# design.net
KiCad netlist of a schematic drawn in EasyEDA Pro
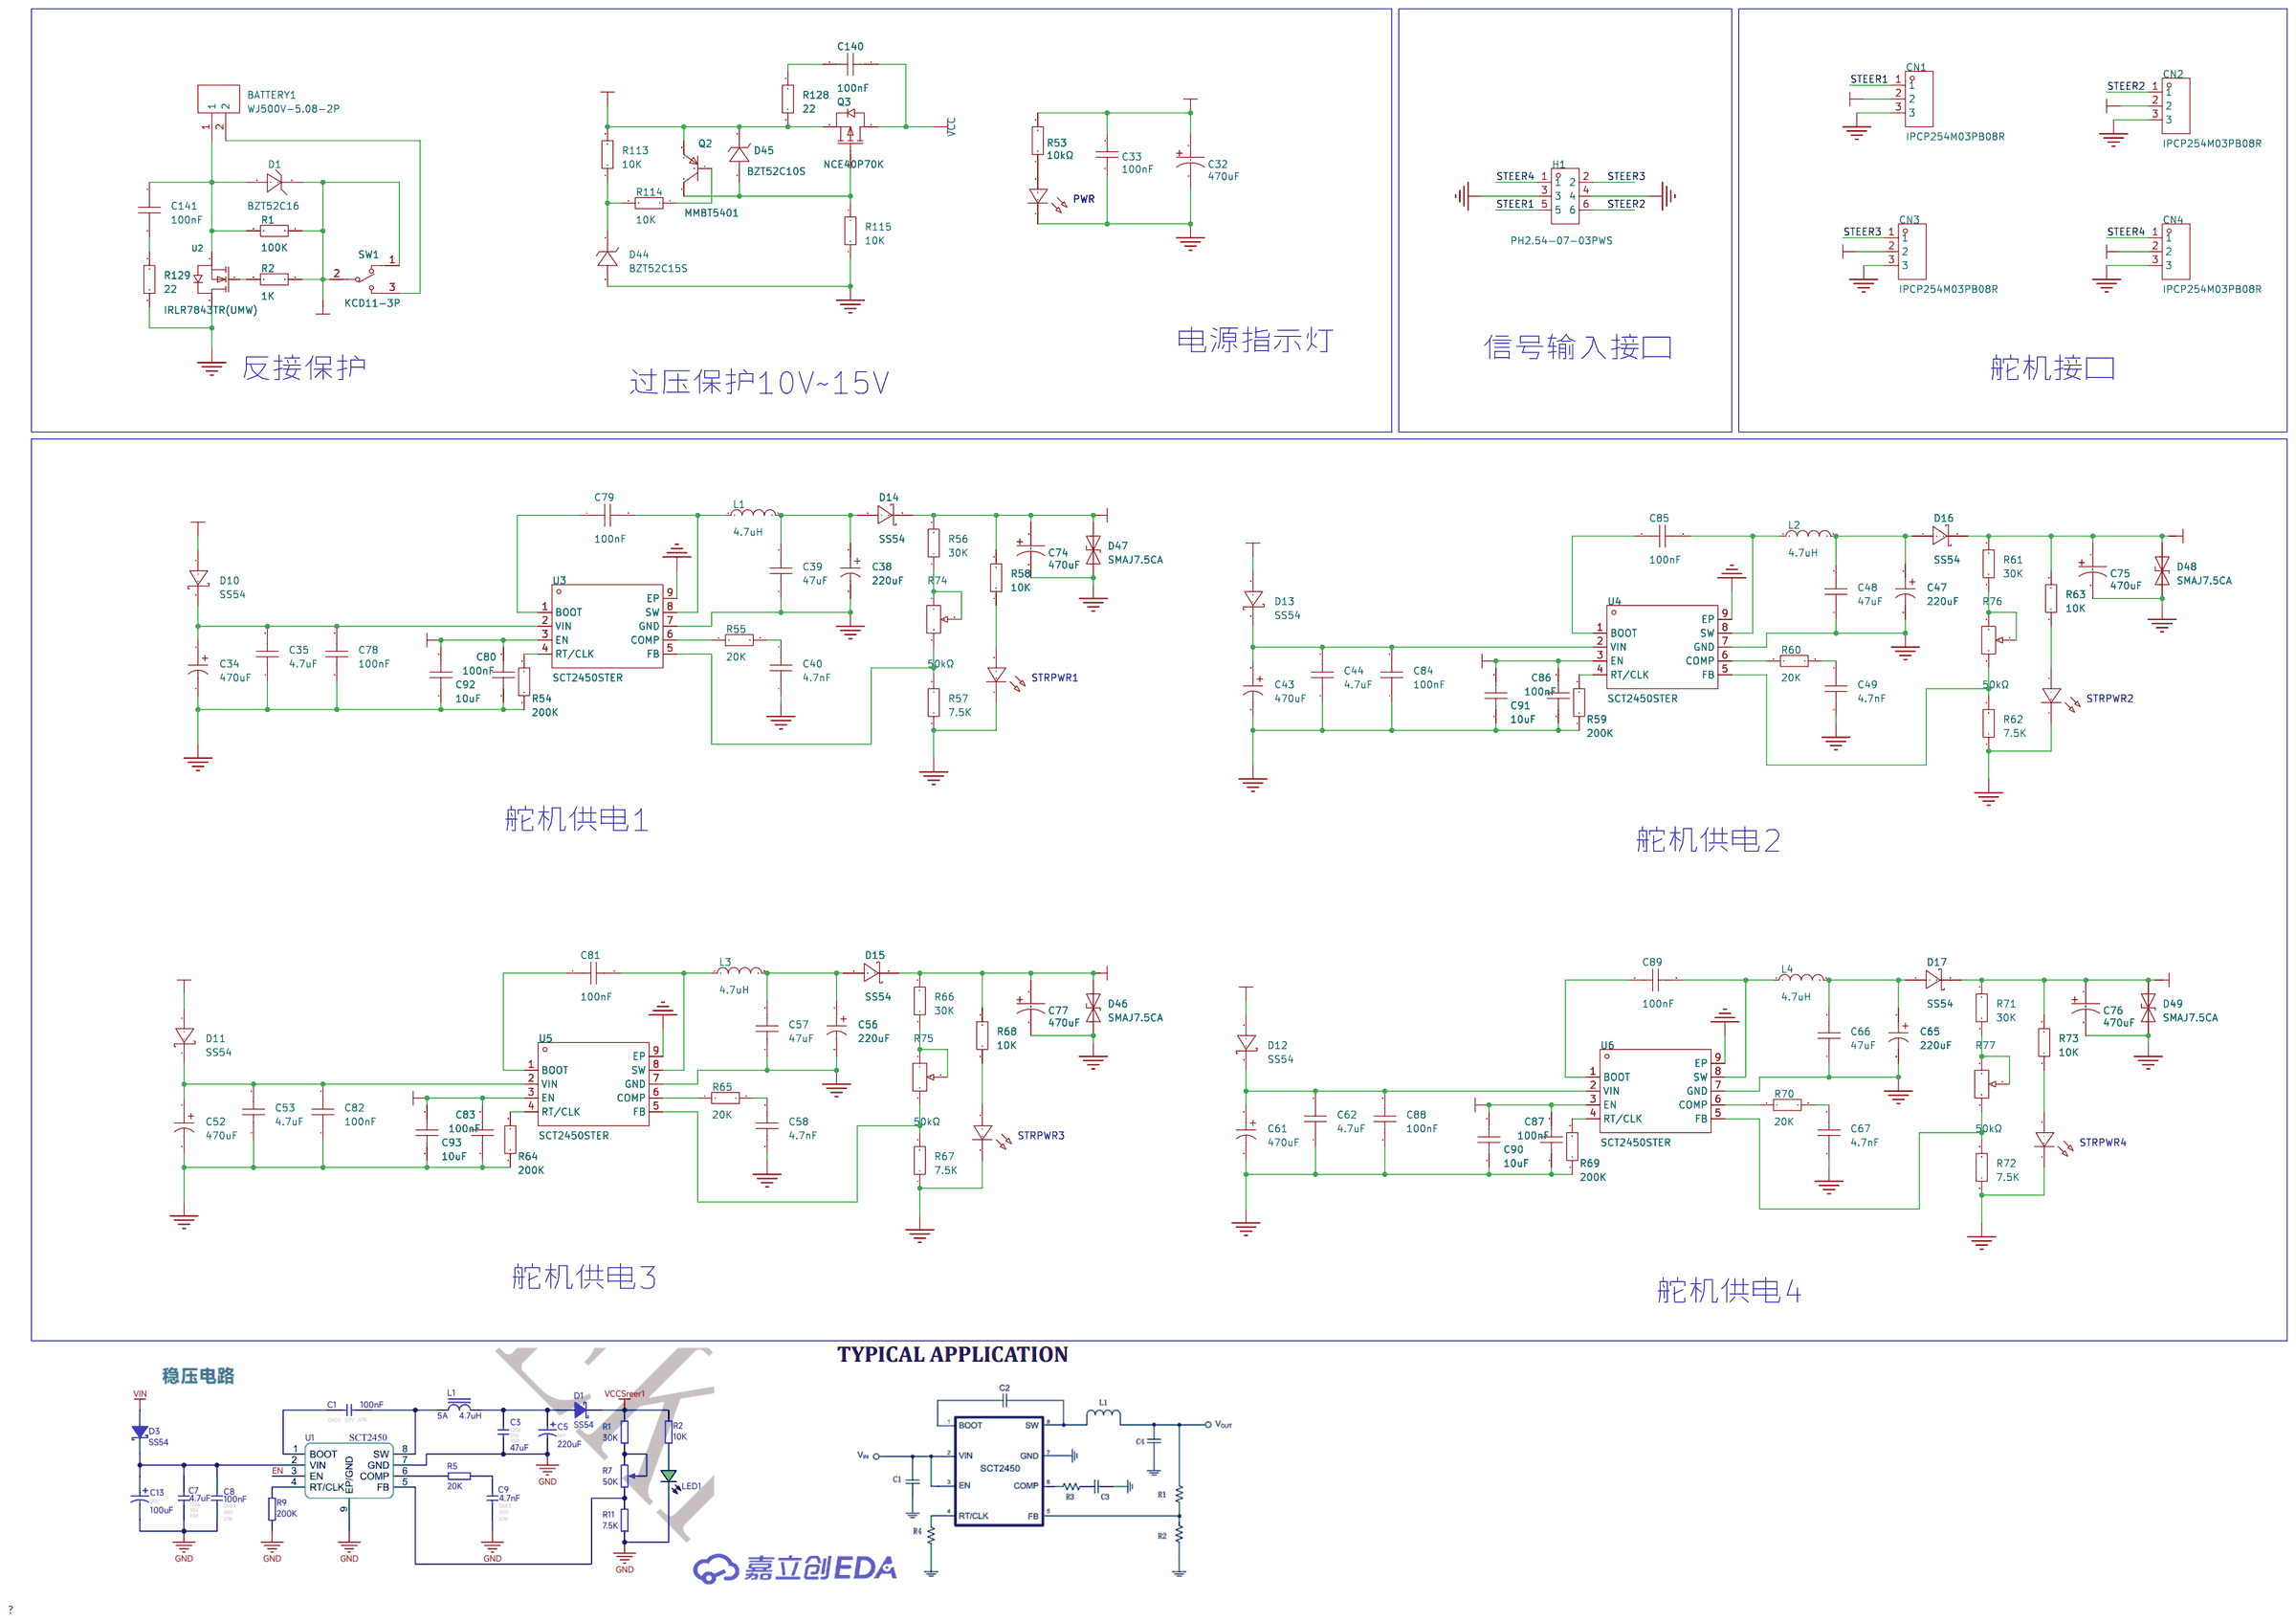
[diagram p0: schematic sheet]

(export (version "E")
  (design (tool "Eeschema 10.0.6"))
  (components
    (comp (ref "BATTERY1")
      (value "WJ500V-5.08-2P")
      (footprint "easyedapro:CONN-TH_2P-P5.00_WJ500V-5.08-2P")
      (fields (field (name "Manufacturer") "KANGNEX(康奈克斯电气)"))
      (libsource (lib "easyedapro") (part "WJ500V-5.08-2P-14-00A"))
    )
    (comp (ref "C32")
      (value "470uF")
      (footprint "easyedapro:CAP-TH_BD8.0-P3.50-D0.6-FD")
      (fields (field (name "Manufacturer Part") "HS1C477M0811PC") (field (name "Manufacturer") "HONOR(荣誉)"))
      (libsource (lib "easyedapro") (part "470uF"))
    )
    (comp (ref "C33")
      (value "100nF")
      (footprint "easyedapro:C0805")
      (fields
        (field (name "Manufacturer Part") "CC0805KRX7R9BB104")
        (field (name "Manufacturer") "YAGEO(国巨)")
      )
      (libsource (lib "easyedapro") (part "100nF"))
    )
    (comp (ref "C34")
      (value "470uF")
      (footprint "easyedapro:CAP-SMD_BD8.0-L8.3-W8.3-FD")
      (description "容值:470uF;精度:±20%;额定电压:25V;纹波电流:280mA@120Hz;等效串联电阻:-;")
      (fields (field (name "Manufacturer Part") "RST470UF25V032") (field (name "Manufacturer") "KNSCHA(科尼盛)"))
      (libsource (lib "easyedapro") (part "RST470UF25V032"))
    )
    (comp (ref "C35")
      (value "4.7uF")
      (footprint "easyedapro:C1206")
      (libsource (lib "easyedapro") (part "CapAcitance"))
    )
    (comp (ref "C38")
      (value "220uF")
      (footprint "easyedapro:CAP-SMD_BD8.0-L8.3-W8.3-FD")
      (description "容值:470uF;精度:±20%;额定电压:25V;纹波电流:280mA@120Hz;等效串联电阻:-;")
      (fields (field (name "Manufacturer Part") "RST470UF25V032") (field (name "Manufacturer") "KNSCHA(科尼盛)"))
      (libsource (lib "easyedapro") (part "RST470UF25V032"))
    )
    (comp (ref "C39")
      (value "47uF")
      (footprint "easyedapro:C1206")
      (libsource (lib "easyedapro") (part "CapAcitance"))
    )
    (comp (ref "C40")
      (value "4.7nF")
      (footprint "easyedapro:C1206")
      (libsource (lib "easyedapro") (part "CapAcitance"))
    )
    (comp (ref "C43")
      (value "470uF")
      (footprint "easyedapro:CAP-SMD_BD8.0-L8.3-W8.3-FD")
      (description "容值:470uF;精度:±20%;额定电压:25V;纹波电流:280mA@120Hz;等效串联电阻:-;")
      (fields (field (name "Manufacturer Part") "RST470UF25V032") (field (name "Manufacturer") "KNSCHA(科尼盛)"))
      (libsource (lib "easyedapro") (part "RST470UF25V032"))
    )
    (comp (ref "C44")
      (value "4.7uF")
      (footprint "easyedapro:C1206")
      (libsource (lib "easyedapro") (part "CapAcitance"))
    )
    (comp (ref "C47")
      (value "220uF")
      (footprint "easyedapro:CAP-SMD_BD8.0-L8.3-W8.3-FD")
      (description "容值:470uF;精度:±20%;额定电压:25V;纹波电流:280mA@120Hz;等效串联电阻:-;")
      (fields (field (name "Manufacturer Part") "RST470UF25V032") (field (name "Manufacturer") "KNSCHA(科尼盛)"))
      (libsource (lib "easyedapro") (part "RST470UF25V032"))
    )
    (comp (ref "C48")
      (value "47uF")
      (footprint "easyedapro:C1206")
      (libsource (lib "easyedapro") (part "CapAcitance"))
    )
    (comp (ref "C49")
      (value "4.7nF")
      (footprint "easyedapro:C1206")
      (libsource (lib "easyedapro") (part "CapAcitance"))
    )
    (comp (ref "C52")
      (value "470uF")
      (footprint "easyedapro:CAP-SMD_BD8.0-L8.3-W8.3-FD")
      (description "容值:470uF;精度:±20%;额定电压:25V;纹波电流:280mA@120Hz;等效串联电阻:-;")
      (fields (field (name "Manufacturer Part") "RST470UF25V032") (field (name "Manufacturer") "KNSCHA(科尼盛)"))
      (libsource (lib "easyedapro") (part "RST470UF25V032"))
    )
    (comp (ref "C53")
      (value "4.7uF")
      (footprint "easyedapro:C1206")
      (libsource (lib "easyedapro") (part "CapAcitance"))
    )
    (comp (ref "C56")
      (value "220uF")
      (footprint "easyedapro:CAP-SMD_BD8.0-L8.3-W8.3-FD")
      (description "容值:470uF;精度:±20%;额定电压:25V;纹波电流:280mA@120Hz;等效串联电阻:-;")
      (fields (field (name "Manufacturer Part") "RST470UF25V032") (field (name "Manufacturer") "KNSCHA(科尼盛)"))
      (libsource (lib "easyedapro") (part "RST470UF25V032"))
    )
    (comp (ref "C57")
      (value "47uF")
      (footprint "easyedapro:C1206")
      (libsource (lib "easyedapro") (part "CapAcitance"))
    )
    (comp (ref "C58")
      (value "4.7nF")
      (footprint "easyedapro:C1206")
      (libsource (lib "easyedapro") (part "CapAcitance"))
    )
    (comp (ref "C61")
      (value "470uF")
      (footprint "easyedapro:CAP-SMD_BD8.0-L8.3-W8.3-FD")
      (description "容值:470uF;精度:±20%;额定电压:25V;纹波电流:280mA@120Hz;等效串联电阻:-;")
      (fields (field (name "Manufacturer Part") "RST470UF25V032") (field (name "Manufacturer") "KNSCHA(科尼盛)"))
      (libsource (lib "easyedapro") (part "RST470UF25V032"))
    )
    (comp (ref "C62")
      (value "4.7uF")
      (footprint "easyedapro:C1206")
      (libsource (lib "easyedapro") (part "CapAcitance"))
    )
    (comp (ref "C65")
      (value "220uF")
      (footprint "easyedapro:CAP-SMD_BD8.0-L8.3-W8.3-FD")
      (description "容值:470uF;精度:±20%;额定电压:25V;纹波电流:280mA@120Hz;等效串联电阻:-;")
      (fields (field (name "Manufacturer Part") "RST470UF25V032") (field (name "Manufacturer") "KNSCHA(科尼盛)"))
      (libsource (lib "easyedapro") (part "RST470UF25V032"))
    )
    (comp (ref "C66")
      (value "47uF")
      (footprint "easyedapro:C1206")
      (libsource (lib "easyedapro") (part "CapAcitance"))
    )
    (comp (ref "C67")
      (value "4.7nF")
      (footprint "easyedapro:C1206")
      (libsource (lib "easyedapro") (part "CapAcitance"))
    )
    (comp (ref "C74")
      (value "470uF")
      (footprint "easyedapro:CAP-TH_BD8.0-P3.50-D0.6-FD")
      (fields (field (name "Manufacturer Part") "HS1C477M0811PC") (field (name "Manufacturer") "HONOR(荣誉)"))
      (libsource (lib "easyedapro") (part "470uF"))
    )
    (comp (ref "C75")
      (value "470uF")
      (footprint "easyedapro:CAP-TH_BD8.0-P3.50-D0.6-FD")
      (fields (field (name "Manufacturer Part") "HS1C477M0811PC") (field (name "Manufacturer") "HONOR(荣誉)"))
      (libsource (lib "easyedapro") (part "470uF"))
    )
    (comp (ref "C76")
      (value "470uF")
      (footprint "easyedapro:CAP-TH_BD8.0-P3.50-D0.6-FD")
      (fields (field (name "Manufacturer Part") "HS1C477M0811PC") (field (name "Manufacturer") "HONOR(荣誉)"))
      (libsource (lib "easyedapro") (part "470uF"))
    )
    (comp (ref "C77")
      (value "470uF")
      (footprint "easyedapro:CAP-TH_BD8.0-P3.50-D0.6-FD")
      (fields (field (name "Manufacturer Part") "HS1C477M0811PC") (field (name "Manufacturer") "HONOR(荣誉)"))
      (libsource (lib "easyedapro") (part "470uF"))
    )
    (comp (ref "C78")
      (value "100nF")
      (footprint "easyedapro:C1206")
      (libsource (lib "easyedapro") (part "CapAcitance"))
    )
    (comp (ref "C79")
      (value "100nF")
      (footprint "easyedapro:C1206")
      (libsource (lib "easyedapro") (part "CapAcitance"))
    )
    (comp (ref "C80")
      (value "100nF")
      (footprint "easyedapro:C1206")
      (libsource (lib "easyedapro") (part "CapAcitance"))
    )
    (comp (ref "C81")
      (value "100nF")
      (footprint "easyedapro:C1206")
      (libsource (lib "easyedapro") (part "CapAcitance"))
    )
    (comp (ref "C82")
      (value "100nF")
      (footprint "easyedapro:C1206")
      (libsource (lib "easyedapro") (part "CapAcitance"))
    )
    (comp (ref "C83")
      (value "100nF")
      (footprint "easyedapro:C1206")
      (libsource (lib "easyedapro") (part "CapAcitance"))
    )
    (comp (ref "C84")
      (value "100nF")
      (footprint "easyedapro:C1206")
      (libsource (lib "easyedapro") (part "CapAcitance"))
    )
    (comp (ref "C85")
      (value "100nF")
      (footprint "easyedapro:C1206")
      (libsource (lib "easyedapro") (part "CapAcitance"))
    )
    (comp (ref "C86")
      (value "100nF")
      (footprint "easyedapro:C1206")
      (libsource (lib "easyedapro") (part "CapAcitance"))
    )
    (comp (ref "C87")
      (value "100nF")
      (footprint "easyedapro:C1206")
      (libsource (lib "easyedapro") (part "CapAcitance"))
    )
    (comp (ref "C88")
      (value "100nF")
      (footprint "easyedapro:C1206")
      (libsource (lib "easyedapro") (part "CapAcitance"))
    )
    (comp (ref "C89")
      (value "100nF")
      (footprint "easyedapro:C1206")
      (libsource (lib "easyedapro") (part "CapAcitance"))
    )
    (comp (ref "C90")
      (value "10uF")
      (footprint "easyedapro:C1206")
      (libsource (lib "easyedapro") (part "CapAcitance"))
    )
    (comp (ref "C91")
      (value "10uF")
      (footprint "easyedapro:C1206")
      (libsource (lib "easyedapro") (part "CapAcitance"))
    )
    (comp (ref "C92")
      (value "10uF")
      (footprint "easyedapro:C1206")
      (libsource (lib "easyedapro") (part "CapAcitance"))
    )
    (comp (ref "C93")
      (value "10uF")
      (footprint "easyedapro:C1206")
      (libsource (lib "easyedapro") (part "CapAcitance"))
    )
    (comp (ref "C140")
      (value "100nF")
      (footprint "easyedapro:C1206")
      (libsource (lib "easyedapro") (part "CapAcitance"))
    )
    (comp (ref "C141")
      (value "100nF")
      (footprint "easyedapro:C1206")
      (libsource (lib "easyedapro") (part "CapAcitance"))
    )
    (comp (ref "CN1")
      (value "IPCP254M03PB08R")
      (footprint "easyedapro:HDR-TH_3P-P2.54-H-M-W10.4")
      (fields (field (name "Manufacturer") "INCP"))
      (libsource (lib "easyedapro") (part "IPCP254M03PB08R"))
    )
    (comp (ref "CN2")
      (value "IPCP254M03PB08R")
      (footprint "easyedapro:HDR-TH_3P-P2.54-H-M-W10.4")
      (fields (field (name "Manufacturer") "INCP"))
      (libsource (lib "easyedapro") (part "IPCP254M03PB08R"))
    )
    (comp (ref "CN3")
      (value "IPCP254M03PB08R")
      (footprint "easyedapro:HDR-TH_3P-P2.54-H-M-W10.4")
      (fields (field (name "Manufacturer") "INCP"))
      (libsource (lib "easyedapro") (part "IPCP254M03PB08R"))
    )
    (comp (ref "CN4")
      (value "IPCP254M03PB08R")
      (footprint "easyedapro:HDR-TH_3P-P2.54-H-M-W10.4")
      (fields (field (name "Manufacturer") "INCP"))
      (libsource (lib "easyedapro") (part "IPCP254M03PB08R"))
    )
    (comp (ref "D1")
      (value "BZT52C16")
      (footprint "easyedapro:SOD-123_L2.7-W1.6-LS3.7-RD")
      (description "二极管配置:独立式;稳压值(标称值):16V;稳压值(范围):15.3V~17.1V;功率:500mW;精度:-;")
      (fields (field (name "Manufacturer") "BORN(伯恩半导体)"))
      (libsource (lib "easyedapro") (part "BZT52C16_C266570"))
    )
    (comp (ref "D10")
      (value "SS54")
      (footprint "easyedapro:SMA_L4.4-W2.8-LS5.4-R-RD")
      (description "二极管配置:独立式;正向压降(Vf):550mV@5A;直流反向耐压(Vr):40V;整流电流:5A;")
      (fields (field (name "Manufacturer") "MDD(辰达半导体)"))
      (libsource (lib "easyedapro") (part "SS54_C22452"))
    )
    (comp (ref "D11")
      (value "SS54")
      (footprint "easyedapro:SMA_L4.4-W2.8-LS5.4-R-RD")
      (description "二极管配置:独立式;正向压降(Vf):550mV@5A;直流反向耐压(Vr):40V;整流电流:5A;")
      (fields (field (name "Manufacturer") "MDD(辰达半导体)"))
      (libsource (lib "easyedapro") (part "SS54_C22452"))
    )
    (comp (ref "D12")
      (value "SS54")
      (footprint "easyedapro:SMA_L4.4-W2.8-LS5.4-R-RD")
      (description "二极管配置:独立式;正向压降(Vf):550mV@5A;直流反向耐压(Vr):40V;整流电流:5A;")
      (fields (field (name "Manufacturer") "MDD(辰达半导体)"))
      (libsource (lib "easyedapro") (part "SS54_C22452"))
    )
    (comp (ref "D13")
      (value "SS54")
      (footprint "easyedapro:SMA_L4.4-W2.8-LS5.4-R-RD")
      (description "二极管配置:独立式;正向压降(Vf):550mV@5A;直流反向耐压(Vr):40V;整流电流:5A;")
      (fields (field (name "Manufacturer") "MDD(辰达半导体)"))
      (libsource (lib "easyedapro") (part "SS54_C22452"))
    )
    (comp (ref "D14")
      (value "SS54")
      (footprint "easyedapro:SMA_L4.4-W2.8-LS5.4-R-RD")
      (description "二极管配置:独立式;正向压降(Vf):550mV@5A;直流反向耐压(Vr):40V;整流电流:5A;")
      (fields (field (name "Manufacturer") "MDD(辰达半导体)"))
      (libsource (lib "easyedapro") (part "SS54_C22452"))
    )
    (comp (ref "D15")
      (value "SS54")
      (footprint "easyedapro:SMA_L4.4-W2.8-LS5.4-R-RD")
      (description "二极管配置:独立式;正向压降(Vf):550mV@5A;直流反向耐压(Vr):40V;整流电流:5A;")
      (fields (field (name "Manufacturer") "MDD(辰达半导体)"))
      (libsource (lib "easyedapro") (part "SS54_C22452"))
    )
    (comp (ref "D16")
      (value "SS54")
      (footprint "easyedapro:SMA_L4.4-W2.8-LS5.4-R-RD")
      (description "二极管配置:独立式;正向压降(Vf):550mV@5A;直流反向耐压(Vr):40V;整流电流:5A;")
      (fields (field (name "Manufacturer") "MDD(辰达半导体)"))
      (libsource (lib "easyedapro") (part "SS54_C22452"))
    )
    (comp (ref "D17")
      (value "SS54")
      (footprint "easyedapro:SMA_L4.4-W2.8-LS5.4-R-RD")
      (description "二极管配置:独立式;正向压降(Vf):550mV@5A;直流反向耐压(Vr):40V;整流电流:5A;")
      (fields (field (name "Manufacturer") "MDD(辰达半导体)"))
      (libsource (lib "easyedapro") (part "SS54_C22452"))
    )
    (comp (ref "D44")
      (value "BZT52C15S")
      (footprint "easyedapro:SOD-323_L1.7-W1.3-LS2.6-RD")
      (description "二极管配置:独立式;稳压值(标称值):15V;稳压值(范围):13.8V~15.6V;功率(Pd):200mW;")
      (fields (field (name "Manufacturer") "宏迦橙"))
      (libsource (lib "easyedapro") (part "BZT52C15S_C19077448"))
    )
    (comp (ref "D45")
      (value "BZT52C10S")
      (footprint "easyedapro:SOD-323_L1.7-W1.3-LS2.6-RD")
      (description "二极管配置:独立式;稳压值(标称值):10V;稳压值(范围):9.4V~10.6V;耗散功率(Pd):200mW;")
      (fields (field (name "Manufacturer") "宏嘉诚"))
      (libsource (lib "easyedapro") (part "BZT52C10S_C19077446"))
    )
    (comp (ref "D46")
      (value "SMAJ7.5CA")
      (footprint "easyedapro:SMA_L4.4-W2.6-LS5.0-BI")
      (description "反向截止电压(Vrwm):7.5V;最大钳位电压:12.9V;峰值脉冲电流(Ipp):31A;击穿电压:8.33V;")
      (fields (field (name "Manufacturer") "JJW(捷捷微)"))
      (libsource (lib "easyedapro") (part "SMAJ7.5CA_C356752"))
    )
    (comp (ref "D47")
      (value "SMAJ7.5CA")
      (footprint "easyedapro:SMA_L4.4-W2.6-LS5.0-BI")
      (description "反向截止电压(Vrwm):7.5V;最大钳位电压:12.9V;峰值脉冲电流(Ipp):31A;击穿电压:8.33V;")
      (fields (field (name "Manufacturer") "JJW(捷捷微)"))
      (libsource (lib "easyedapro") (part "SMAJ7.5CA_C356752"))
    )
    (comp (ref "D48")
      (value "SMAJ7.5CA")
      (footprint "easyedapro:SMA_L4.4-W2.6-LS5.0-BI")
      (description "反向截止电压(Vrwm):7.5V;最大钳位电压:12.9V;峰值脉冲电流(Ipp):31A;击穿电压:8.33V;")
      (fields (field (name "Manufacturer") "JJW(捷捷微)"))
      (libsource (lib "easyedapro") (part "SMAJ7.5CA_C356752"))
    )
    (comp (ref "D49")
      (value "SMAJ7.5CA")
      (footprint "easyedapro:SMA_L4.4-W2.6-LS5.0-BI")
      (description "反向截止电压(Vrwm):7.5V;最大钳位电压:12.9V;峰值脉冲电流(Ipp):31A;击穿电压:8.33V;")
      (fields (field (name "Manufacturer") "JJW(捷捷微)"))
      (libsource (lib "easyedapro") (part "SMAJ7.5CA_C356752"))
    )
    (comp (ref "H1")
      (value "PH2.54-07-03PWS")
      (footprint "easyedapro:HDR-TH_6P-P2.54-H-M-R2-C3-S2.54-W12.3-N")
      (fields (field (name "Manufacturer") "XUNPU(讯普)"))
      (libsource (lib "easyedapro") (part "PH2.54-07-03PWS"))
    )
    (comp (ref "L1")
      (value "4.7uH")
      (footprint "easyedapro:IND-SMD_L7.4-W6.6")
      (description "电感值:4.7uH;精度:-;额定电流:5.5A;饱和电流(Isat):6.5A;类型:一体成型电感;")
      (fields (field (name "Manufacturer Part") "HMS0603-4R7") (field (name "Manufacturer") "增益"))
      (libsource (lib "easyedapro") (part "HMS0603-4R7"))
    )
    (comp (ref "L2")
      (value "4.7uH")
      (footprint "easyedapro:IND-SMD_L7.4-W6.6")
      (description "电感值:4.7uH;精度:-;额定电流:5.5A;饱和电流(Isat):6.5A;类型:一体成型电感;")
      (fields (field (name "Manufacturer Part") "HMS0603-4R7") (field (name "Manufacturer") "增益"))
      (libsource (lib "easyedapro") (part "HMS0603-4R7"))
    )
    (comp (ref "L3")
      (value "4.7uH")
      (footprint "easyedapro:IND-SMD_L7.4-W6.6")
      (description "电感值:4.7uH;精度:-;额定电流:5.5A;饱和电流(Isat):6.5A;类型:一体成型电感;")
      (fields (field (name "Manufacturer Part") "HMS0603-4R7") (field (name "Manufacturer") "增益"))
      (libsource (lib "easyedapro") (part "HMS0603-4R7"))
    )
    (comp (ref "L4")
      (value "4.7uH")
      (footprint "easyedapro:IND-SMD_L7.4-W6.6")
      (description "电感值:4.7uH;精度:-;额定电流:5.5A;饱和电流(Isat):6.5A;类型:一体成型电感;")
      (fields (field (name "Manufacturer Part") "HMS0603-4R7") (field (name "Manufacturer") "增益"))
      (libsource (lib "easyedapro") (part "HMS0603-4R7"))
    )
    (comp (ref "PWR")
      (value "~")
      (footprint "easyedapro:LED_0805")
      (libsource (lib "easyedapro") (part "LED_G"))
    )
    (comp (ref "Q2")
      (value "MMBT5401")
      (footprint "easyedapro:SOT-23-3_L2.9-W1.3-P1.90-LS2.4-BR")
      (description "晶体管类型:PNP;集电极电流(Ic):600mA;集射极击穿电压(Vceo):160V;耗散功率(Pd):300mW;直流电流增益(hFE):100@10mA,5.0V;")
      (fields (field (name "Manufacturer") "宏嘉诚"))
      (libsource (lib "easyedapro") (part "MMBT5401_C7420356"))
    )
    (comp (ref "Q3")
      (value "NCE40P70K")
      (footprint "easyedapro:TO-252-2_L6.6-W6.1-P4.57-LS9.9-TL-CW")
      (fields (field (name "Manufacturer") "NCE(无锡新洁能)"))
      (libsource (lib "easyedapro") (part "NCE40P70K"))
    )
    (comp (ref "R1") (value "100K") (footprint "easyedapro:R0805") (libsource (lib "easyedapro") (part "电阻")))
    (comp (ref "R2") (value "1K") (footprint "easyedapro:R0805") (libsource (lib "easyedapro") (part "电阻")))
    (comp (ref "R53")
      (value "10kΩ")
      (footprint "easyedapro:R0805")
      (fields
        (field (name "Manufacturer Part") "0805W8F1002T5E")
        (field (name "Manufacturer") "UNI-ROYAL(厚声)")
      )
      (libsource (lib "easyedapro") (part "10kΩ"))
    )
    (comp (ref "R54")
      (value "200K")
      (footprint "easyedapro:R0603")
      (libsource (lib "easyedapro") (part "电阻"))
    )
    (comp (ref "R55") (value "20K") (footprint "easyedapro:R0603") (libsource (lib "easyedapro") (part "电阻")))
    (comp (ref "R56") (value "30K") (footprint "easyedapro:R0603") (libsource (lib "easyedapro") (part "电阻")))
    (comp (ref "R57")
      (value "7.5K")
      (footprint "easyedapro:R0603")
      (libsource (lib "easyedapro") (part "电阻"))
    )
    (comp (ref "R58") (value "10K") (footprint "easyedapro:R0603") (libsource (lib "easyedapro") (part "电阻")))
    (comp (ref "R59")
      (value "200K")
      (footprint "easyedapro:R0603")
      (libsource (lib "easyedapro") (part "电阻"))
    )
    (comp (ref "R60") (value "20K") (footprint "easyedapro:R0603") (libsource (lib "easyedapro") (part "电阻")))
    (comp (ref "R61") (value "30K") (footprint "easyedapro:R0603") (libsource (lib "easyedapro") (part "电阻")))
    (comp (ref "R62")
      (value "7.5K")
      (footprint "easyedapro:R0603")
      (libsource (lib "easyedapro") (part "电阻"))
    )
    (comp (ref "R63") (value "10K") (footprint "easyedapro:R0603") (libsource (lib "easyedapro") (part "电阻")))
    (comp (ref "R64")
      (value "200K")
      (footprint "easyedapro:R0603")
      (libsource (lib "easyedapro") (part "电阻"))
    )
    (comp (ref "R65") (value "20K") (footprint "easyedapro:R0603") (libsource (lib "easyedapro") (part "电阻")))
    (comp (ref "R66") (value "30K") (footprint "easyedapro:R0603") (libsource (lib "easyedapro") (part "电阻")))
    (comp (ref "R67")
      (value "7.5K")
      (footprint "easyedapro:R0603")
      (libsource (lib "easyedapro") (part "电阻"))
    )
    (comp (ref "R68") (value "10K") (footprint "easyedapro:R0603") (libsource (lib "easyedapro") (part "电阻")))
    (comp (ref "R69")
      (value "200K")
      (footprint "easyedapro:R0603")
      (libsource (lib "easyedapro") (part "电阻"))
    )
    (comp (ref "R70") (value "20K") (footprint "easyedapro:R0603") (libsource (lib "easyedapro") (part "电阻")))
    (comp (ref "R71") (value "30K") (footprint "easyedapro:R0603") (libsource (lib "easyedapro") (part "电阻")))
    (comp (ref "R72")
      (value "7.5K")
      (footprint "easyedapro:R0603")
      (libsource (lib "easyedapro") (part "电阻"))
    )
    (comp (ref "R73") (value "10K") (footprint "easyedapro:R0603") (libsource (lib "easyedapro") (part "电阻")))
    (comp (ref "R74")
      (value "50kΩ")
      (footprint "easyedapro:RES-ADJ-TH_3P-L7.1-W6.9-P2.50-L_3362P")
      (description "阻值:50kΩ;精度:±10%;")
      (fields (field (name "Manufacturer Part") "3362P-1-503") (field (name "Manufacturer") "BOCHEN(博晨)"))
      (libsource (lib "easyedapro") (part "3362P-1-503"))
    )
    (comp (ref "R75")
      (value "50kΩ")
      (footprint "easyedapro:RES-ADJ-TH_3P-L7.1-W6.9-P2.50-L_3362P")
      (description "阻值:50kΩ;精度:±10%;")
      (fields (field (name "Manufacturer Part") "3362P-1-503") (field (name "Manufacturer") "BOCHEN(博晨)"))
      (libsource (lib "easyedapro") (part "3362P-1-503"))
    )
    (comp (ref "R76")
      (value "50kΩ")
      (footprint "easyedapro:RES-ADJ-TH_3P-L7.1-W6.9-P2.50-L_3362P")
      (description "阻值:50kΩ;精度:±10%;")
      (fields (field (name "Manufacturer Part") "3362P-1-503") (field (name "Manufacturer") "BOCHEN(博晨)"))
      (libsource (lib "easyedapro") (part "3362P-1-503"))
    )
    (comp (ref "R77")
      (value "50kΩ")
      (footprint "easyedapro:RES-ADJ-TH_3P-L7.1-W6.9-P2.50-L_3362P")
      (description "阻值:50kΩ;精度:±10%;")
      (fields (field (name "Manufacturer Part") "3362P-1-503") (field (name "Manufacturer") "BOCHEN(博晨)"))
      (libsource (lib "easyedapro") (part "3362P-1-503"))
    )
    (comp (ref "R113")
      (value "10K")
      (footprint "easyedapro:R0805")
      (libsource (lib "easyedapro") (part "电阻"))
    )
    (comp (ref "R114")
      (value "10K")
      (footprint "easyedapro:R0805")
      (libsource (lib "easyedapro") (part "电阻"))
    )
    (comp (ref "R115")
      (value "10K")
      (footprint "easyedapro:R0805")
      (libsource (lib "easyedapro") (part "电阻"))
    )
    (comp (ref "R128") (value "22") (footprint "easyedapro:R0603") (libsource (lib "easyedapro") (part "电阻")))
    (comp (ref "R129") (value "22") (footprint "easyedapro:R0603") (libsource (lib "easyedapro") (part "电阻")))
    (comp (ref "STRPWR1")
      (value "~")
      (footprint "easyedapro:LED_0805")
      (libsource (lib "easyedapro") (part "LED_G"))
    )
    (comp (ref "STRPWR2")
      (value "~")
      (footprint "easyedapro:LED_0805")
      (libsource (lib "easyedapro") (part "LED_G"))
    )
    (comp (ref "STRPWR3")
      (value "~")
      (footprint "easyedapro:LED_0805")
      (libsource (lib "easyedapro") (part "LED_G"))
    )
    (comp (ref "STRPWR4")
      (value "~")
      (footprint "easyedapro:LED_0805")
      (libsource (lib "easyedapro") (part "LED_G"))
    )
    (comp (ref "SW1")
      (value "KCD11-3P")
      (footprint "easyedapro:KCD11-3P")
      (libsource (lib "easyedapro") (part "KCD11-3P"))
    )
    (comp (ref "U2")
      (value "IRLR7843TR(UMW)")
      (footprint "easyedapro:TO-252-2_L6.5-W6.1-P4.58-LS10.0-BL")
      (fields (field (name "Manufacturer") "UMW(友台半导体)"))
      (libsource (lib "easyedapro") (part "IRLR7843TR(UMW)"))
    )
    (comp (ref "U3")
      (value "SCT2450STER")
      (footprint "easyedapro:ESOP-8_L4.9-W3.9-P1.27-LS6.0-BL-EP")
      (description "功能类型:降压型;工作电压:3.8V~36V;输出电流:5A;")
      (fields (field (name "Manufacturer") "SCT(芯洲科技)"))
      (libsource (lib "easyedapro") (part "SCT2450STER"))
    )
    (comp (ref "U4")
      (value "SCT2450STER")
      (footprint "easyedapro:ESOP-8_L4.9-W3.9-P1.27-LS6.0-BL-EP")
      (description "功能类型:降压型;工作电压:3.8V~36V;输出电流:5A;")
      (fields (field (name "Manufacturer") "SCT(芯洲科技)"))
      (libsource (lib "easyedapro") (part "SCT2450STER"))
    )
    (comp (ref "U5")
      (value "SCT2450STER")
      (footprint "easyedapro:ESOP-8_L4.9-W3.9-P1.27-LS6.0-BL-EP")
      (description "功能类型:降压型;工作电压:3.8V~36V;输出电流:5A;")
      (fields (field (name "Manufacturer") "SCT(芯洲科技)"))
      (libsource (lib "easyedapro") (part "SCT2450STER"))
    )
    (comp (ref "U6")
      (value "SCT2450STER")
      (footprint "easyedapro:ESOP-8_L4.9-W3.9-P1.27-LS6.0-BL-EP")
      (description "功能类型:降压型;工作电压:3.8V~36V;输出电流:5A;")
      (fields (field (name "Manufacturer") "SCT(芯洲科技)"))
      (libsource (lib "easyedapro") (part "SCT2450STER"))
    )
  )
  (nets
    (net (code "1") (name "/STEER1") (class "Default")
      (node (ref "CN1") (pin "1") (pinfunction "1_1") (pintype "unspecified"))
      (node (ref "H1") (pin "5") (pinfunction "5_5") (pintype "unspecified"))
    )
    (net (code "2") (name "/STEER2") (class "Default")
      (node (ref "CN2") (pin "1") (pinfunction "1_1") (pintype "unspecified"))
      (node (ref "H1") (pin "6") (pinfunction "6_6") (pintype "unspecified"))
    )
    (net (code "3") (name "/STEER3") (class "Default")
      (node (ref "CN3") (pin "1") (pinfunction "1_1") (pintype "unspecified"))
      (node (ref "H1") (pin "2") (pinfunction "2_2") (pintype "unspecified"))
    )
    (net (code "4") (name "/STEER4") (class "Default")
      (node (ref "CN4") (pin "1") (pinfunction "1_1") (pintype "unspecified"))
      (node (ref "H1") (pin "1") (pinfunction "1_1") (pintype "unspecified"))
    )
    (net (code "5") (name "GND") (class "Default")
      (node (ref "C32") (pin "2") (pinfunction "2_2") (pintype "unspecified"))
      (node (ref "C33") (pin "1") (pinfunction "1_1") (pintype "input"))
      (node (ref "C34") (pin "2") (pinfunction "2_2") (pintype "input"))
      (node (ref "C35") (pin "1") (pinfunction "1_1") (pintype "input"))
      (node (ref "C38") (pin "2") (pinfunction "2_2") (pintype "input"))
      (node (ref "C39") (pin "1") (pinfunction "1_1") (pintype "input"))
      (node (ref "C40") (pin "1") (pinfunction "1_1") (pintype "input"))
      (node (ref "C43") (pin "2") (pinfunction "2_2") (pintype "input"))
      (node (ref "C44") (pin "1") (pinfunction "1_1") (pintype "input"))
      (node (ref "C47") (pin "2") (pinfunction "2_2") (pintype "input"))
      (node (ref "C48") (pin "1") (pinfunction "1_1") (pintype "input"))
      (node (ref "C49") (pin "1") (pinfunction "1_1") (pintype "input"))
      (node (ref "C52") (pin "2") (pinfunction "2_2") (pintype "input"))
      (node (ref "C53") (pin "1") (pinfunction "1_1") (pintype "input"))
      (node (ref "C56") (pin "2") (pinfunction "2_2") (pintype "input"))
      (node (ref "C57") (pin "1") (pinfunction "1_1") (pintype "input"))
      (node (ref "C58") (pin "1") (pinfunction "1_1") (pintype "input"))
      (node (ref "C61") (pin "2") (pinfunction "2_2") (pintype "input"))
      (node (ref "C62") (pin "1") (pinfunction "1_1") (pintype "input"))
      (node (ref "C65") (pin "2") (pinfunction "2_2") (pintype "input"))
      (node (ref "C66") (pin "1") (pinfunction "1_1") (pintype "input"))
      (node (ref "C67") (pin "1") (pinfunction "1_1") (pintype "input"))
      (node (ref "C74") (pin "2") (pinfunction "2_2") (pintype "unspecified"))
      (node (ref "C75") (pin "2") (pinfunction "2_2") (pintype "unspecified"))
      (node (ref "C76") (pin "2") (pinfunction "2_2") (pintype "unspecified"))
      (node (ref "C77") (pin "2") (pinfunction "2_2") (pintype "unspecified"))
      (node (ref "C78") (pin "1") (pinfunction "1_1") (pintype "input"))
      (node (ref "C80") (pin "1") (pinfunction "1_1") (pintype "input"))
      (node (ref "C82") (pin "1") (pinfunction "1_1") (pintype "input"))
      (node (ref "C83") (pin "1") (pinfunction "1_1") (pintype "input"))
      (node (ref "C84") (pin "1") (pinfunction "1_1") (pintype "input"))
      (node (ref "C86") (pin "1") (pinfunction "1_1") (pintype "input"))
      (node (ref "C87") (pin "1") (pinfunction "1_1") (pintype "input"))
      (node (ref "C88") (pin "1") (pinfunction "1_1") (pintype "input"))
      (node (ref "C90") (pin "1") (pinfunction "1_1") (pintype "input"))
      (node (ref "C91") (pin "1") (pinfunction "1_1") (pintype "input"))
      (node (ref "C92") (pin "1") (pinfunction "1_1") (pintype "input"))
      (node (ref "C93") (pin "1") (pinfunction "1_1") (pintype "input"))
      (node (ref "CN1") (pin "3") (pinfunction "3_3") (pintype "unspecified"))
      (node (ref "CN2") (pin "3") (pinfunction "3_3") (pintype "unspecified"))
      (node (ref "CN3") (pin "3") (pinfunction "3_3") (pintype "unspecified"))
      (node (ref "CN4") (pin "3") (pinfunction "3_3") (pintype "unspecified"))
      (node (ref "D44") (pin "2") (pinfunction "A_2") (pintype "unspecified"))
      (node (ref "D46") (pin "1") (pinfunction "K_1") (pintype "unspecified"))
      (node (ref "D47") (pin "1") (pinfunction "K_1") (pintype "unspecified"))
      (node (ref "D48") (pin "1") (pinfunction "K_1") (pintype "unspecified"))
      (node (ref "D49") (pin "1") (pinfunction "K_1") (pintype "unspecified"))
      (node (ref "H1") (pin "3") (pinfunction "3_3") (pintype "unspecified"))
      (node (ref "H1") (pin "4") (pinfunction "4_4") (pintype "unspecified"))
      (node (ref "PWR") (pin "1") (pinfunction "C_1") (pintype "input"))
      (node (ref "R115") (pin "2") (pinfunction "2_2") (pintype "input"))
      (node (ref "R129") (pin "2") (pinfunction "2_2") (pintype "input"))
      (node (ref "R54") (pin "1") (pinfunction "1_1") (pintype "input"))
      (node (ref "R57") (pin "1") (pinfunction "1_1") (pintype "input"))
      (node (ref "R59") (pin "1") (pinfunction "1_1") (pintype "input"))
      (node (ref "R62") (pin "1") (pinfunction "1_1") (pintype "input"))
      (node (ref "R64") (pin "1") (pinfunction "1_1") (pintype "input"))
      (node (ref "R67") (pin "1") (pinfunction "1_1") (pintype "input"))
      (node (ref "R69") (pin "1") (pinfunction "1_1") (pintype "input"))
      (node (ref "R72") (pin "1") (pinfunction "1_1") (pintype "input"))
      (node (ref "STRPWR1") (pin "1") (pinfunction "C_1") (pintype "input"))
      (node (ref "STRPWR2") (pin "1") (pinfunction "C_1") (pintype "input"))
      (node (ref "STRPWR3") (pin "1") (pinfunction "C_1") (pintype "input"))
      (node (ref "STRPWR4") (pin "1") (pinfunction "C_1") (pintype "input"))
      (node (ref "U2") (pin "2") (pinfunction "D_2") (pintype "input"))
      (node (ref "U3") (pin "7") (pinfunction "GND_7") (pintype "unspecified"))
      (node (ref "U3") (pin "9") (pinfunction "EP_9") (pintype "unspecified"))
      (node (ref "U4") (pin "7") (pinfunction "GND_7") (pintype "unspecified"))
      (node (ref "U4") (pin "9") (pinfunction "EP_9") (pintype "unspecified"))
      (node (ref "U5") (pin "7") (pinfunction "GND_7") (pintype "unspecified"))
      (node (ref "U5") (pin "9") (pinfunction "EP_9") (pintype "unspecified"))
      (node (ref "U6") (pin "7") (pinfunction "GND_7") (pintype "unspecified"))
      (node (ref "U6") (pin "9") (pinfunction "EP_9") (pintype "unspecified"))
    )
    (net (code "6") (name "Net-(BATTERY1-Pad2)") (class "Default")
      (node (ref "BATTERY1") (pin "2") (pinfunction "2_2") (pintype "unspecified"))
      (node (ref "SW1") (pin "3") (pinfunction "3_3") (pintype "unspecified"))
    )
    (net (code "7") (name "Net-(C40-Pad2)") (class "Default")
      (node (ref "C40") (pin "2") (pinfunction "2_2") (pintype "input"))
      (node (ref "R55") (pin "2") (pinfunction "2_2") (pintype "input"))
    )
    (net (code "8") (name "Net-(C49-Pad2)") (class "Default")
      (node (ref "C49") (pin "2") (pinfunction "2_2") (pintype "input"))
      (node (ref "R60") (pin "2") (pinfunction "2_2") (pintype "input"))
    )
    (net (code "9") (name "Net-(C58-Pad2)") (class "Default")
      (node (ref "C58") (pin "2") (pinfunction "2_2") (pintype "input"))
      (node (ref "R65") (pin "2") (pinfunction "2_2") (pintype "input"))
    )
    (net (code "10") (name "Net-(C67-Pad2)") (class "Default")
      (node (ref "C67") (pin "2") (pinfunction "2_2") (pintype "input"))
      (node (ref "R70") (pin "2") (pinfunction "2_2") (pintype "input"))
    )
    (net (code "11") (name "Net-(C140-Pad2)") (class "Default")
      (node (ref "C140") (pin "2") (pinfunction "2_2") (pintype "input"))
      (node (ref "R128") (pin "1") (pinfunction "1_1") (pintype "input"))
    )
    (net (code "12") (name "Net-(C141-Pad2)") (class "Default")
      (node (ref "C141") (pin "2") (pinfunction "2_2") (pintype "input"))
      (node (ref "R129") (pin "1") (pinfunction "1_1") (pintype "input"))
    )
    (net (code "13") (name "Net-(D10-K)") (class "Default")
      (node (ref "C34") (pin "1") (pinfunction "1_1") (pintype "input"))
      (node (ref "C35") (pin "2") (pinfunction "2_2") (pintype "input"))
      (node (ref "C78") (pin "2") (pinfunction "2_2") (pintype "input"))
      (node (ref "D10") (pin "2") (pinfunction "K_2") (pintype "unspecified"))
      (node (ref "U3") (pin "2") (pinfunction "VIN_2") (pintype "unspecified"))
    )
    (net (code "14") (name "Net-(D11-K)") (class "Default")
      (node (ref "C52") (pin "1") (pinfunction "1_1") (pintype "input"))
      (node (ref "C53") (pin "2") (pinfunction "2_2") (pintype "input"))
      (node (ref "C82") (pin "2") (pinfunction "2_2") (pintype "input"))
      (node (ref "D11") (pin "2") (pinfunction "K_2") (pintype "unspecified"))
      (node (ref "U5") (pin "2") (pinfunction "VIN_2") (pintype "unspecified"))
    )
    (net (code "15") (name "Net-(D12-K)") (class "Default")
      (node (ref "C61") (pin "1") (pinfunction "1_1") (pintype "input"))
      (node (ref "C62") (pin "2") (pinfunction "2_2") (pintype "input"))
      (node (ref "C88") (pin "2") (pinfunction "2_2") (pintype "input"))
      (node (ref "D12") (pin "2") (pinfunction "K_2") (pintype "unspecified"))
      (node (ref "U6") (pin "2") (pinfunction "VIN_2") (pintype "unspecified"))
    )
    (net (code "16") (name "Net-(D13-K)") (class "Default")
      (node (ref "C43") (pin "1") (pinfunction "1_1") (pintype "input"))
      (node (ref "C44") (pin "2") (pinfunction "2_2") (pintype "input"))
      (node (ref "C84") (pin "2") (pinfunction "2_2") (pintype "input"))
      (node (ref "D13") (pin "2") (pinfunction "K_2") (pintype "unspecified"))
      (node (ref "U4") (pin "2") (pinfunction "VIN_2") (pintype "unspecified"))
    )
    (net (code "17") (name "Net-(D14-A)") (class "Default")
      (node (ref "C38") (pin "1") (pinfunction "1_1") (pintype "input"))
      (node (ref "C39") (pin "2") (pinfunction "2_2") (pintype "input"))
      (node (ref "D14") (pin "1") (pinfunction "A_1") (pintype "unspecified"))
      (node (ref "L1") (pin "2") (pinfunction "2_2") (pintype "unspecified"))
    )
    (net (code "18") (name "Net-(D15-A)") (class "Default")
      (node (ref "C56") (pin "1") (pinfunction "1_1") (pintype "input"))
      (node (ref "C57") (pin "2") (pinfunction "2_2") (pintype "input"))
      (node (ref "D15") (pin "1") (pinfunction "A_1") (pintype "unspecified"))
      (node (ref "L3") (pin "2") (pinfunction "2_2") (pintype "unspecified"))
    )
    (net (code "19") (name "Net-(D16-A)") (class "Default")
      (node (ref "C47") (pin "1") (pinfunction "1_1") (pintype "input"))
      (node (ref "C48") (pin "2") (pinfunction "2_2") (pintype "input"))
      (node (ref "D16") (pin "1") (pinfunction "A_1") (pintype "unspecified"))
      (node (ref "L2") (pin "2") (pinfunction "2_2") (pintype "unspecified"))
    )
    (net (code "20") (name "Net-(D17-A)") (class "Default")
      (node (ref "C65") (pin "1") (pinfunction "1_1") (pintype "input"))
      (node (ref "C66") (pin "2") (pinfunction "2_2") (pintype "input"))
      (node (ref "D17") (pin "1") (pinfunction "A_1") (pintype "unspecified"))
      (node (ref "L4") (pin "2") (pinfunction "2_2") (pintype "unspecified"))
    )
    (net (code "21") (name "Net-(D44-K)") (class "Default")
      (node (ref "D44") (pin "1") (pinfunction "K_1") (pintype "unspecified"))
      (node (ref "R113") (pin "1") (pinfunction "1_1") (pintype "input"))
      (node (ref "R114") (pin "2") (pinfunction "2_2") (pintype "input"))
    )
    (net (code "22") (name "Net-(D45-A)") (class "Default")
      (node (ref "D45") (pin "2") (pinfunction "A_2") (pintype "unspecified"))
      (node (ref "Q2") (pin "3") (pinfunction "C_3") (pintype "input"))
      (node (ref "Q3") (pin "1") (pinfunction "G_1") (pintype "unspecified"))
      (node (ref "R115") (pin "1") (pinfunction "1_1") (pintype "input"))
    )
    (net (code "23") (name "Net-(PWR-A)") (class "Default")
      (node (ref "PWR") (pin "2") (pinfunction "A_2") (pintype "input"))
      (node (ref "R53") (pin "1") (pinfunction "1_1") (pintype "input"))
    )
    (net (code "24") (name "Net-(Q2-B)") (class "Default")
      (node (ref "Q2") (pin "1") (pinfunction "B_1") (pintype "input"))
      (node (ref "R114") (pin "1") (pinfunction "1_1") (pintype "input"))
    )
    (net (code "25") (name "Net-(R56-Pad1)") (class "Default")
      (node (ref "R56") (pin "1") (pinfunction "1_1") (pintype "input"))
      (node (ref "R74") (pin "1") (pinfunction "1_1") (pintype "input"))
      (node (ref "R74") (pin "2") (pinfunction "2_2") (pintype "input"))
    )
    (net (code "26") (name "Net-(R61-Pad1)") (class "Default")
      (node (ref "R61") (pin "1") (pinfunction "1_1") (pintype "input"))
      (node (ref "R76") (pin "1") (pinfunction "1_1") (pintype "input"))
      (node (ref "R76") (pin "2") (pinfunction "2_2") (pintype "input"))
    )
    (net (code "27") (name "Net-(R66-Pad1)") (class "Default")
      (node (ref "R66") (pin "1") (pinfunction "1_1") (pintype "input"))
      (node (ref "R75") (pin "1") (pinfunction "1_1") (pintype "input"))
      (node (ref "R75") (pin "2") (pinfunction "2_2") (pintype "input"))
    )
    (net (code "28") (name "Net-(R71-Pad1)") (class "Default")
      (node (ref "R71") (pin "1") (pinfunction "1_1") (pintype "input"))
      (node (ref "R77") (pin "1") (pinfunction "1_1") (pintype "input"))
      (node (ref "R77") (pin "2") (pinfunction "2_2") (pintype "input"))
    )
    (net (code "29") (name "Net-(STRPWR1-A)") (class "Default")
      (node (ref "R58") (pin "1") (pinfunction "1_1") (pintype "input"))
      (node (ref "STRPWR1") (pin "2") (pinfunction "A_2") (pintype "input"))
    )
    (net (code "30") (name "Net-(STRPWR2-A)") (class "Default")
      (node (ref "R63") (pin "1") (pinfunction "1_1") (pintype "input"))
      (node (ref "STRPWR2") (pin "2") (pinfunction "A_2") (pintype "input"))
    )
    (net (code "31") (name "Net-(STRPWR3-A)") (class "Default")
      (node (ref "R68") (pin "1") (pinfunction "1_1") (pintype "input"))
      (node (ref "STRPWR3") (pin "2") (pinfunction "A_2") (pintype "input"))
    )
    (net (code "32") (name "Net-(STRPWR4-A)") (class "Default")
      (node (ref "R73") (pin "1") (pinfunction "1_1") (pintype "input"))
      (node (ref "STRPWR4") (pin "2") (pinfunction "A_2") (pintype "input"))
    )
    (net (code "33") (name "Net-(U2-G)") (class "Default")
      (node (ref "R2") (pin "1") (pinfunction "1_1") (pintype "input"))
      (node (ref "U2") (pin "1") (pinfunction "G_1") (pintype "input"))
    )
    (net (code "34") (name "Net-(U2-S)") (class "Default")
      (node (ref "BATTERY1") (pin "1") (pinfunction "1_1") (pintype "unspecified"))
      (node (ref "C141") (pin "1") (pinfunction "1_1") (pintype "input"))
      (node (ref "D1") (pin "2") (pinfunction "2_2") (pintype "unspecified"))
      (node (ref "R1") (pin "1") (pinfunction "1_1") (pintype "input"))
      (node (ref "U2") (pin "3") (pinfunction "S_3") (pintype "input"))
    )
    (net (code "35") (name "Net-(U3-BOOT)") (class "Default")
      (node (ref "C79") (pin "1") (pinfunction "1_1") (pintype "input"))
      (node (ref "U3") (pin "1") (pinfunction "BOOT_1") (pintype "unspecified"))
    )
    (net (code "36") (name "Net-(U3-COMP)") (class "Default")
      (node (ref "R55") (pin "1") (pinfunction "1_1") (pintype "input"))
      (node (ref "U3") (pin "6") (pinfunction "COMP_6") (pintype "unspecified"))
    )
    (net (code "37") (name "Net-(U3-FB)") (class "Default")
      (node (ref "R57") (pin "2") (pinfunction "2_2") (pintype "input"))
      (node (ref "R74") (pin "3") (pinfunction "3_3") (pintype "input"))
      (node (ref "U3") (pin "5") (pinfunction "FB_5") (pintype "unspecified"))
    )
    (net (code "38") (name "Net-(U3-RT{slash}CLK)") (class "Default")
      (node (ref "R54") (pin "2") (pinfunction "2_2") (pintype "input"))
      (node (ref "U3") (pin "4") (pinfunction "RT/CLK_4") (pintype "unspecified"))
    )
    (net (code "39") (name "Net-(U3-SW)") (class "Default")
      (node (ref "C79") (pin "2") (pinfunction "2_2") (pintype "input"))
      (node (ref "L1") (pin "1") (pinfunction "1_1") (pintype "unspecified"))
      (node (ref "U3") (pin "8") (pinfunction "SW_8") (pintype "unspecified"))
    )
    (net (code "40") (name "Net-(U4-BOOT)") (class "Default")
      (node (ref "C85") (pin "1") (pinfunction "1_1") (pintype "input"))
      (node (ref "U4") (pin "1") (pinfunction "BOOT_1") (pintype "unspecified"))
    )
    (net (code "41") (name "Net-(U4-COMP)") (class "Default")
      (node (ref "R60") (pin "1") (pinfunction "1_1") (pintype "input"))
      (node (ref "U4") (pin "6") (pinfunction "COMP_6") (pintype "unspecified"))
    )
    (net (code "42") (name "Net-(U4-FB)") (class "Default")
      (node (ref "R62") (pin "2") (pinfunction "2_2") (pintype "input"))
      (node (ref "R76") (pin "3") (pinfunction "3_3") (pintype "input"))
      (node (ref "U4") (pin "5") (pinfunction "FB_5") (pintype "unspecified"))
    )
    (net (code "43") (name "Net-(U4-RT{slash}CLK)") (class "Default")
      (node (ref "R59") (pin "2") (pinfunction "2_2") (pintype "input"))
      (node (ref "U4") (pin "4") (pinfunction "RT/CLK_4") (pintype "unspecified"))
    )
    (net (code "44") (name "Net-(U4-SW)") (class "Default")
      (node (ref "C85") (pin "2") (pinfunction "2_2") (pintype "input"))
      (node (ref "L2") (pin "1") (pinfunction "1_1") (pintype "unspecified"))
      (node (ref "U4") (pin "8") (pinfunction "SW_8") (pintype "unspecified"))
    )
    (net (code "45") (name "Net-(U5-BOOT)") (class "Default")
      (node (ref "C81") (pin "1") (pinfunction "1_1") (pintype "input"))
      (node (ref "U5") (pin "1") (pinfunction "BOOT_1") (pintype "unspecified"))
    )
    (net (code "46") (name "Net-(U5-COMP)") (class "Default")
      (node (ref "R65") (pin "1") (pinfunction "1_1") (pintype "input"))
      (node (ref "U5") (pin "6") (pinfunction "COMP_6") (pintype "unspecified"))
    )
    (net (code "47") (name "Net-(U5-FB)") (class "Default")
      (node (ref "R67") (pin "2") (pinfunction "2_2") (pintype "input"))
      (node (ref "R75") (pin "3") (pinfunction "3_3") (pintype "input"))
      (node (ref "U5") (pin "5") (pinfunction "FB_5") (pintype "unspecified"))
    )
    (net (code "48") (name "Net-(U5-RT{slash}CLK)") (class "Default")
      (node (ref "R64") (pin "2") (pinfunction "2_2") (pintype "input"))
      (node (ref "U5") (pin "4") (pinfunction "RT/CLK_4") (pintype "unspecified"))
    )
    (net (code "49") (name "Net-(U5-SW)") (class "Default")
      (node (ref "C81") (pin "2") (pinfunction "2_2") (pintype "input"))
      (node (ref "L3") (pin "1") (pinfunction "1_1") (pintype "unspecified"))
      (node (ref "U5") (pin "8") (pinfunction "SW_8") (pintype "unspecified"))
    )
    (net (code "50") (name "Net-(U6-BOOT)") (class "Default")
      (node (ref "C89") (pin "1") (pinfunction "1_1") (pintype "input"))
      (node (ref "U6") (pin "1") (pinfunction "BOOT_1") (pintype "unspecified"))
    )
    (net (code "51") (name "Net-(U6-COMP)") (class "Default")
      (node (ref "R70") (pin "1") (pinfunction "1_1") (pintype "input"))
      (node (ref "U6") (pin "6") (pinfunction "COMP_6") (pintype "unspecified"))
    )
    (net (code "52") (name "Net-(U6-FB)") (class "Default")
      (node (ref "R72") (pin "2") (pinfunction "2_2") (pintype "input"))
      (node (ref "R77") (pin "3") (pinfunction "3_3") (pintype "input"))
      (node (ref "U6") (pin "5") (pinfunction "FB_5") (pintype "unspecified"))
    )
    (net (code "53") (name "Net-(U6-RT{slash}CLK)") (class "Default")
      (node (ref "R69") (pin "2") (pinfunction "2_2") (pintype "input"))
      (node (ref "U6") (pin "4") (pinfunction "RT/CLK_4") (pintype "unspecified"))
    )
    (net (code "54") (name "Net-(U6-SW)") (class "Default")
      (node (ref "C89") (pin "2") (pinfunction "2_2") (pintype "input"))
      (node (ref "L4") (pin "1") (pinfunction "1_1") (pintype "unspecified"))
      (node (ref "U6") (pin "8") (pinfunction "SW_8") (pintype "unspecified"))
    )
    (net (code "55") (name "VCC") (class "Default")
      (node (ref "C140") (pin "1") (pinfunction "1_1") (pintype "input"))
      (node (ref "C32") (pin "1") (pinfunction "1_1") (pintype "unspecified"))
      (node (ref "C33") (pin "2") (pinfunction "2_2") (pintype "input"))
      (node (ref "C80") (pin "2") (pinfunction "2_2") (pintype "input"))
      (node (ref "C83") (pin "2") (pinfunction "2_2") (pintype "input"))
      (node (ref "C86") (pin "2") (pinfunction "2_2") (pintype "input"))
      (node (ref "C87") (pin "2") (pinfunction "2_2") (pintype "input"))
      (node (ref "C90") (pin "2") (pinfunction "2_2") (pintype "input"))
      (node (ref "C91") (pin "2") (pinfunction "2_2") (pintype "input"))
      (node (ref "C92") (pin "2") (pinfunction "2_2") (pintype "input"))
      (node (ref "C93") (pin "2") (pinfunction "2_2") (pintype "input"))
      (node (ref "D10") (pin "1") (pinfunction "A_1") (pintype "unspecified"))
      (node (ref "D11") (pin "1") (pinfunction "A_1") (pintype "unspecified"))
      (node (ref "D12") (pin "1") (pinfunction "A_1") (pintype "unspecified"))
      (node (ref "D13") (pin "1") (pinfunction "A_1") (pintype "unspecified"))
      (node (ref "Q3") (pin "2") (pinfunction "D_2") (pintype "unspecified"))
      (node (ref "R53") (pin "2") (pinfunction "2_2") (pintype "input"))
      (node (ref "U3") (pin "3") (pinfunction "EN_3") (pintype "unspecified"))
      (node (ref "U4") (pin "3") (pinfunction "EN_3") (pintype "unspecified"))
      (node (ref "U5") (pin "3") (pinfunction "EN_3") (pintype "unspecified"))
      (node (ref "U6") (pin "3") (pinfunction "EN_3") (pintype "unspecified"))
    )
    (net (code "56") (name "VCCBAT") (class "Default")
      (node (ref "D1") (pin "1") (pinfunction "1_1") (pintype "unspecified"))
      (node (ref "D45") (pin "1") (pinfunction "K_1") (pintype "unspecified"))
      (node (ref "Q2") (pin "2") (pinfunction "E_2") (pintype "input"))
      (node (ref "Q3") (pin "3") (pinfunction "S_3") (pintype "unspecified"))
      (node (ref "R1") (pin "2") (pinfunction "2_2") (pintype "input"))
      (node (ref "R113") (pin "2") (pinfunction "2_2") (pintype "input"))
      (node (ref "R128") (pin "2") (pinfunction "2_2") (pintype "input"))
      (node (ref "R2") (pin "2") (pinfunction "2_2") (pintype "input"))
      (node (ref "SW1") (pin "1") (pinfunction "1_1") (pintype "unspecified"))
      (node (ref "SW1") (pin "2") (pinfunction "2_2") (pintype "unspecified"))
    )
    (net (code "57") (name "VCCSTEER1") (class "Default")
      (node (ref "C74") (pin "1") (pinfunction "1_1") (pintype "unspecified"))
      (node (ref "CN1") (pin "2") (pinfunction "2_2") (pintype "unspecified"))
      (node (ref "D14") (pin "2") (pinfunction "K_2") (pintype "unspecified"))
      (node (ref "D47") (pin "2") (pinfunction "A_2") (pintype "unspecified"))
      (node (ref "R56") (pin "2") (pinfunction "2_2") (pintype "input"))
      (node (ref "R58") (pin "2") (pinfunction "2_2") (pintype "input"))
    )
    (net (code "58") (name "VCCSTEER2") (class "Default")
      (node (ref "C75") (pin "1") (pinfunction "1_1") (pintype "unspecified"))
      (node (ref "CN2") (pin "2") (pinfunction "2_2") (pintype "unspecified"))
      (node (ref "D16") (pin "2") (pinfunction "K_2") (pintype "unspecified"))
      (node (ref "D48") (pin "2") (pinfunction "A_2") (pintype "unspecified"))
      (node (ref "R61") (pin "2") (pinfunction "2_2") (pintype "input"))
      (node (ref "R63") (pin "2") (pinfunction "2_2") (pintype "input"))
    )
    (net (code "59") (name "VCCSTEER3") (class "Default")
      (node (ref "C77") (pin "1") (pinfunction "1_1") (pintype "unspecified"))
      (node (ref "CN3") (pin "2") (pinfunction "2_2") (pintype "unspecified"))
      (node (ref "D15") (pin "2") (pinfunction "K_2") (pintype "unspecified"))
      (node (ref "D46") (pin "2") (pinfunction "A_2") (pintype "unspecified"))
      (node (ref "R66") (pin "2") (pinfunction "2_2") (pintype "input"))
      (node (ref "R68") (pin "2") (pinfunction "2_2") (pintype "input"))
    )
    (net (code "60") (name "VCCSTEER4") (class "Default")
      (node (ref "C76") (pin "1") (pinfunction "1_1") (pintype "unspecified"))
      (node (ref "CN4") (pin "2") (pinfunction "2_2") (pintype "unspecified"))
      (node (ref "D17") (pin "2") (pinfunction "K_2") (pintype "unspecified"))
      (node (ref "D49") (pin "2") (pinfunction "A_2") (pintype "unspecified"))
      (node (ref "R71") (pin "2") (pinfunction "2_2") (pintype "input"))
      (node (ref "R73") (pin "2") (pinfunction "2_2") (pintype "input"))
    )
  )
)
